# STRWL-S03-V00-CAN_MAIN.net
KiCad netlist of a schematic drawn in Altium Designer
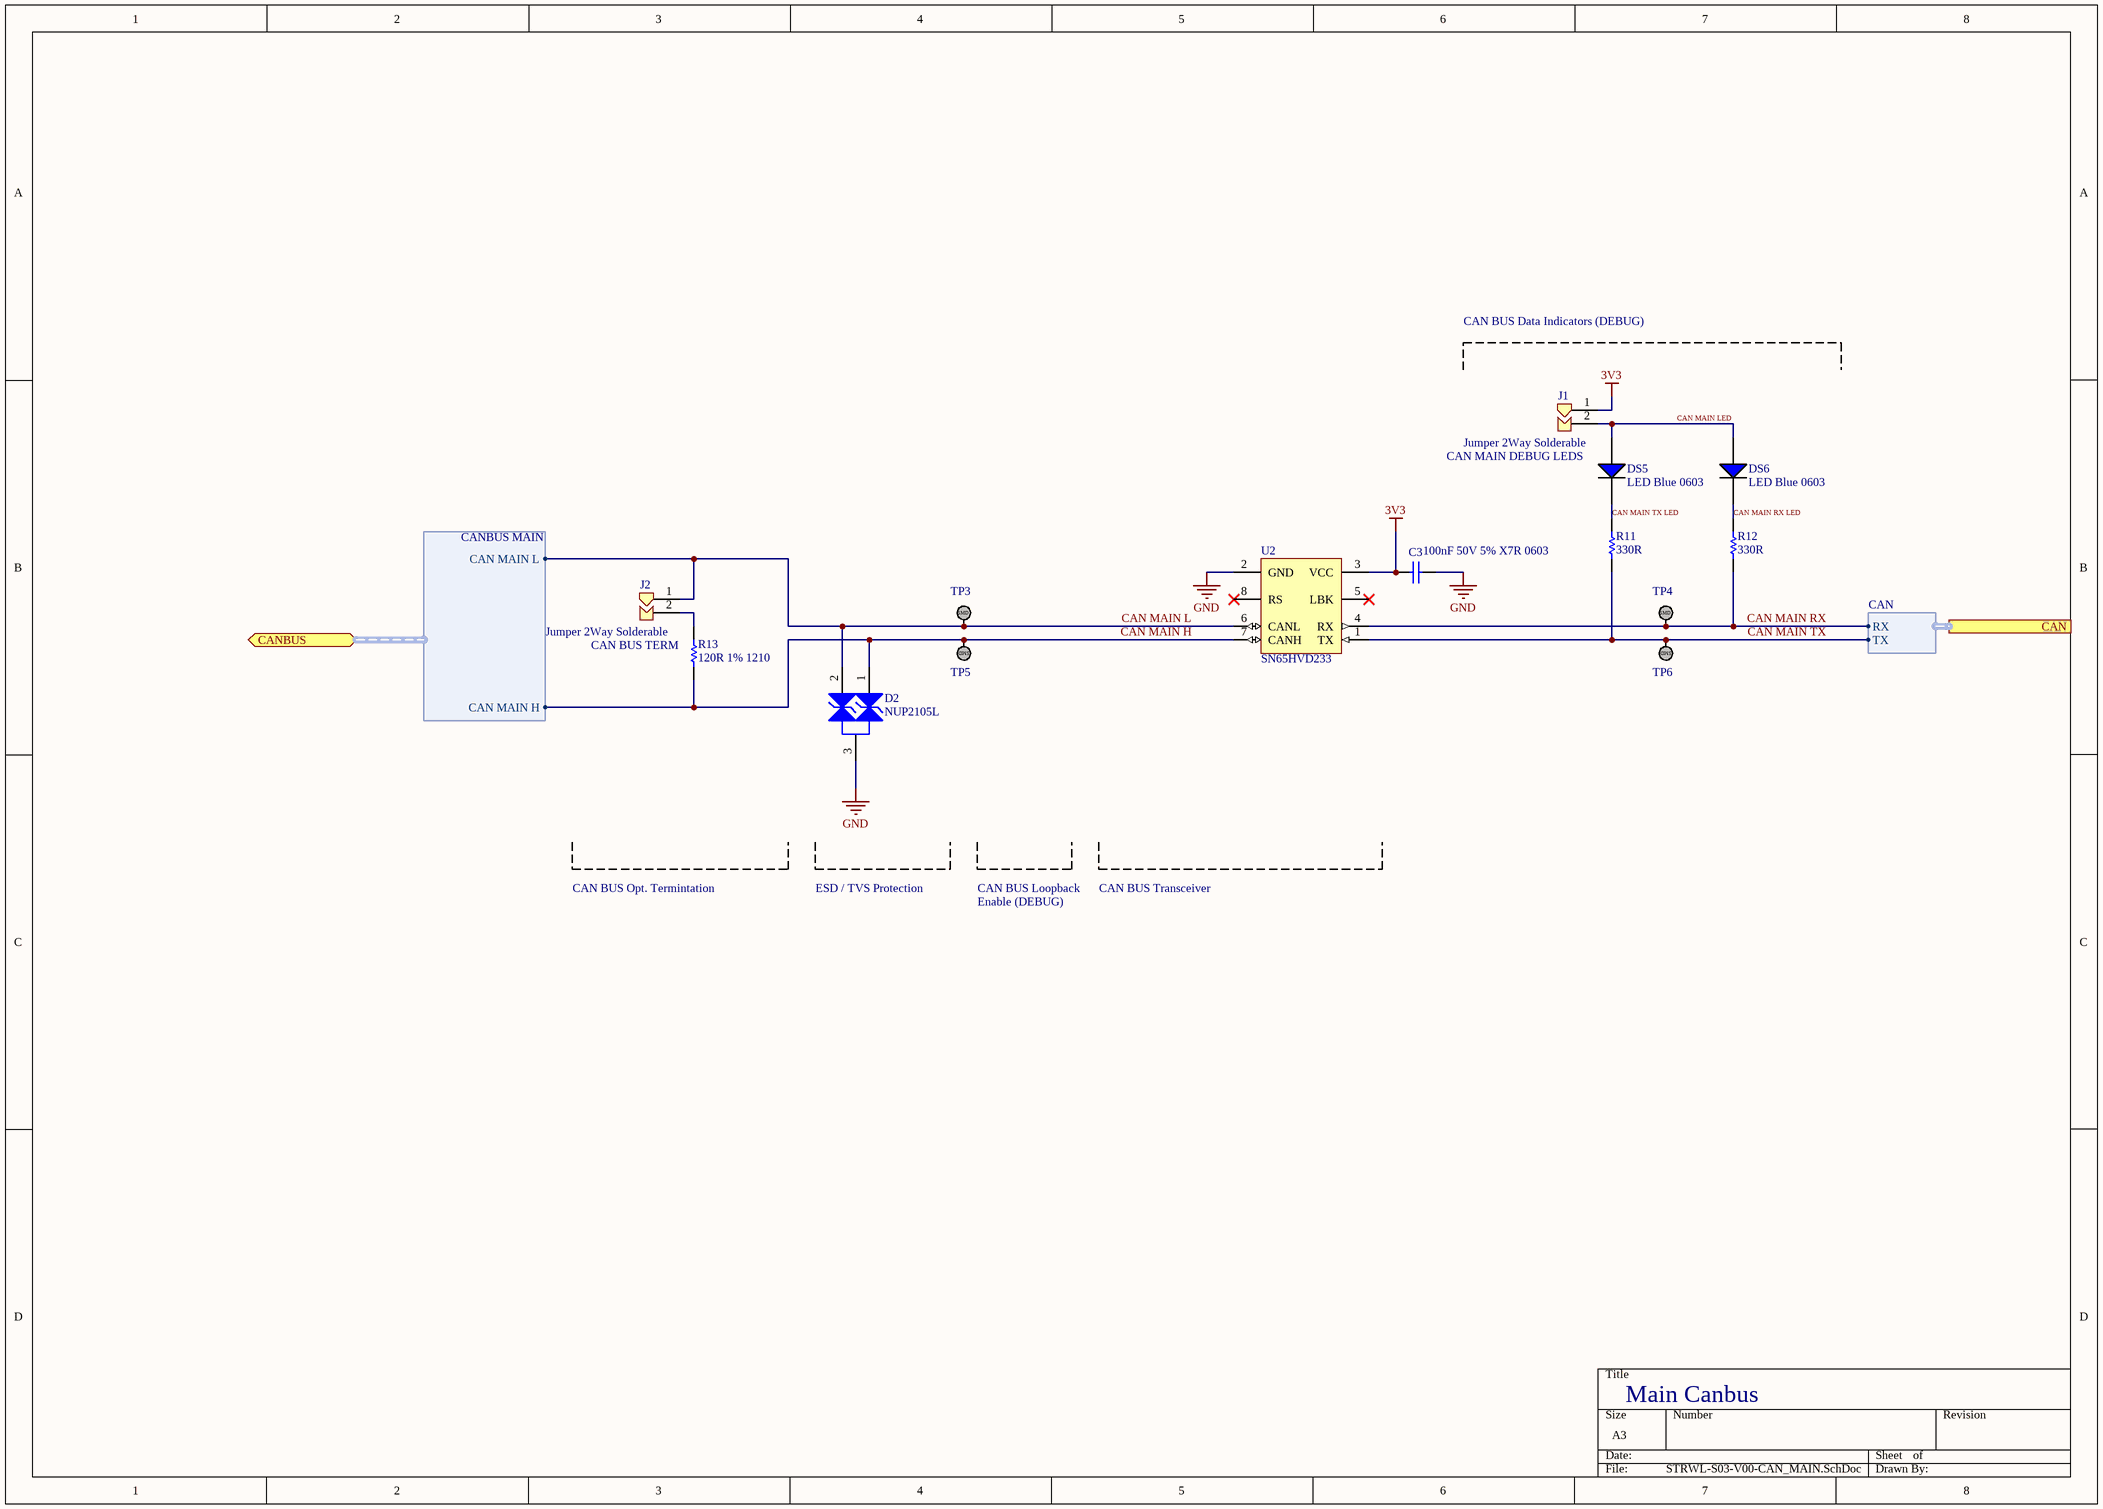
[diagram p0: STRWL-S03-V00-CAN_MAIN.SchDoc]

(export (version "E")
  (design (tool "Eeschema 10.0.6"))
  (components
    (comp (ref "C3")
      (value "100nF 50V 5% X7R 0603")
      (footprint "Cap_Ceramic_0603")
      (description "Capacitor, Ceramic, SMD, 100nF, 50V, 5%, X7R, 0603")
      (libsource (lib "StandardCapacitors") (part "100nF 50V 5% X7R 0603"))
    )
    (comp (ref "D2")
      (value "NUP2105L")
      (footprint "NUP2105L")
      (libsource (lib "QUTMS_CANLibrary") (part "NUP2105L"))
    )
    (comp (ref "DS5")
      (value "LED Blue 0603")
      (footprint "LED BLUE 0603")
      (libsource (lib "QUTMS_LEDLibrary") (part "LED BLUE 0603"))
    )
    (comp (ref "DS6")
      (value "LED Blue 0603")
      (footprint "LED BLUE 0603")
      (libsource (lib "QUTMS_LEDLibrary") (part "LED BLUE 0603"))
    )
    (comp (ref "J1")
      (value "Jumper 2Way Solderable")
      (footprint "Jumper_2Way_Solderable")
      (description "Jumper 2Way Side Solderable")
      (libsource (lib "QUTMS_JumperLibrary") (part "Jumper 2Way Side Solderable"))
    )
    (comp (ref "J2")
      (value "Jumper 2Way Solderable")
      (footprint "Jumper_2Way_Solderable")
      (description "Jumper 2Way Side Solderable")
      (libsource (lib "QUTMS_JumperLibrary") (part "Jumper 2Way Side Solderable"))
    )
    (comp (ref "R11")
      (value "330R")
      (footprint "Res_ThinFilm_0603")
      (description "Resistor, SMD, 330R, 0.1W, 5%, 0603")
      (libsource (lib "StandardResistors") (part "330R 5% 0603"))
    )
    (comp (ref "R12")
      (value "330R")
      (footprint "Res_ThinFilm_0603")
      (description "Resistor, SMD, 330R, 0.1W, 5%, 0603")
      (libsource (lib "StandardResistors") (part "330R 5% 0603"))
    )
    (comp (ref "R13")
      (value "120R 1% 1210")
      (footprint "Res_ThinFilm_1210")
      (description "Resistor, SMD, 120R, 0.25W, 1%, 1210")
      (libsource (lib "StandardResistors") (part "120R 1% 1210"))
    )
    (comp (ref "TP3")
      (value "TestPoint_SMD")
      (footprint "TestPointSMD")
      (libsource (lib "StandardTest") (part "TestPoint_SMD"))
    )
    (comp (ref "TP4")
      (value "TestPoint_SMD")
      (footprint "TestPointSMD")
      (libsource (lib "StandardTest") (part "TestPoint_SMD"))
    )
    (comp (ref "TP5")
      (value "TestPoint_SMD")
      (footprint "TestPointSMD")
      (libsource (lib "StandardTest") (part "TestPoint_SMD"))
    )
    (comp (ref "TP6")
      (value "TestPoint_SMD")
      (footprint "TestPointSMD")
      (libsource (lib "StandardTest") (part "TestPoint_SMD"))
    )
    (comp (ref "U2")
      (value "SN65HVD233")
      (footprint "SN65HVD233DR")
      (libsource (lib "altium-import") (part "root_2_SN65HVD233_"))
    )
  )
  (nets
    (net (code "4") (name "/CAN MAIN H") (class "Default")
      (node (ref "D2") (pin "1") (pinfunction "1_1") (pintype "passive"))
      (node (ref "R13") (pin "1") (pinfunction "1_1") (pintype "passive"))
      (node (ref "TP5") (pin "1") (pinfunction "1_1") (pintype "passive"))
      (node (ref "U2") (pin "7") (pinfunction "CANH_7") (pintype "bidirectional"))
    )
    (net (code "5") (name "/CAN MAIN L") (class "Default")
      (node (ref "D2") (pin "2") (pinfunction "2_2") (pintype "passive"))
      (node (ref "J2") (pin "1") (pinfunction "1_1") (pintype "passive"))
      (node (ref "TP3") (pin "1") (pinfunction "1_1") (pintype "passive"))
      (node (ref "U2") (pin "6") (pinfunction "CANL_6") (pintype "bidirectional"))
    )
    (net (code "6") (name "/CAN MAIN LED") (class "Default")
      (node (ref "DS5") (pin "1") (pinfunction "A_1") (pintype "passive"))
      (node (ref "DS6") (pin "1") (pinfunction "A_1") (pintype "passive"))
      (node (ref "J1") (pin "2") (pinfunction "2_2") (pintype "passive"))
    )
    (net (code "7") (name "/CAN MAIN RX") (class "Default")
      (node (ref "R12") (pin "1") (pinfunction "1_1") (pintype "passive"))
      (node (ref "TP4") (pin "1") (pinfunction "1_1") (pintype "passive"))
      (node (ref "U2") (pin "4") (pinfunction "RX_4") (pintype "output"))
    )
    (net (code "8") (name "/CAN MAIN RX LED") (class "Default")
      (node (ref "DS6") (pin "2") (pinfunction "C_2") (pintype "passive"))
      (node (ref "R12") (pin "2") (pinfunction "2_2") (pintype "passive"))
    )
    (net (code "9") (name "/CAN MAIN TX") (class "Default")
      (node (ref "R11") (pin "1") (pinfunction "1_1") (pintype "passive"))
      (node (ref "TP6") (pin "1") (pinfunction "1_1") (pintype "passive"))
      (node (ref "U2") (pin "1") (pinfunction "TX_1") (pintype "input"))
    )
    (net (code "10") (name "/CAN MAIN TX LED") (class "Default")
      (node (ref "DS5") (pin "2") (pinfunction "C_2") (pintype "passive"))
      (node (ref "R11") (pin "2") (pinfunction "2_2") (pintype "passive"))
    )
    (net (code "13") (name "3V3") (class "Default")
      (node (ref "C3") (pin "1") (pinfunction "1_1") (pintype "passive"))
      (node (ref "J1") (pin "1") (pinfunction "1_1") (pintype "passive"))
      (node (ref "U2") (pin "3") (pinfunction "VCC_3") (pintype "passive"))
    )
    (net (code "14") (name "GND") (class "Default")
      (node (ref "C3") (pin "2") (pinfunction "2_2") (pintype "passive"))
      (node (ref "D2") (pin "3") (pinfunction "3_3") (pintype "passive"))
      (node (ref "U2") (pin "2") (pinfunction "GND_2") (pintype "passive"))
    )
    (net (code "15") (name "Net-(J2-Pad2)") (class "Default")
      (node (ref "J2") (pin "2") (pinfunction "2_2") (pintype "passive"))
      (node (ref "R13") (pin "2") (pinfunction "2_2") (pintype "passive"))
    )
    (net (code "16") (name "unconnected-(U2-LBK-Pad5)") (class "Default")
      (node (ref "U2") (pin "5") (pinfunction "LBK_5") (pintype "passive+no_connect"))
    )
    (net (code "17") (name "unconnected-(U2-RS-Pad8)") (class "Default")
      (node (ref "U2") (pin "8") (pinfunction "RS_8") (pintype "passive+no_connect"))
    )
  )
)
